# 68_Ethernet-GEPHY_RGMII1.net
KiCad netlist of a schematic drawn in Altium Designer
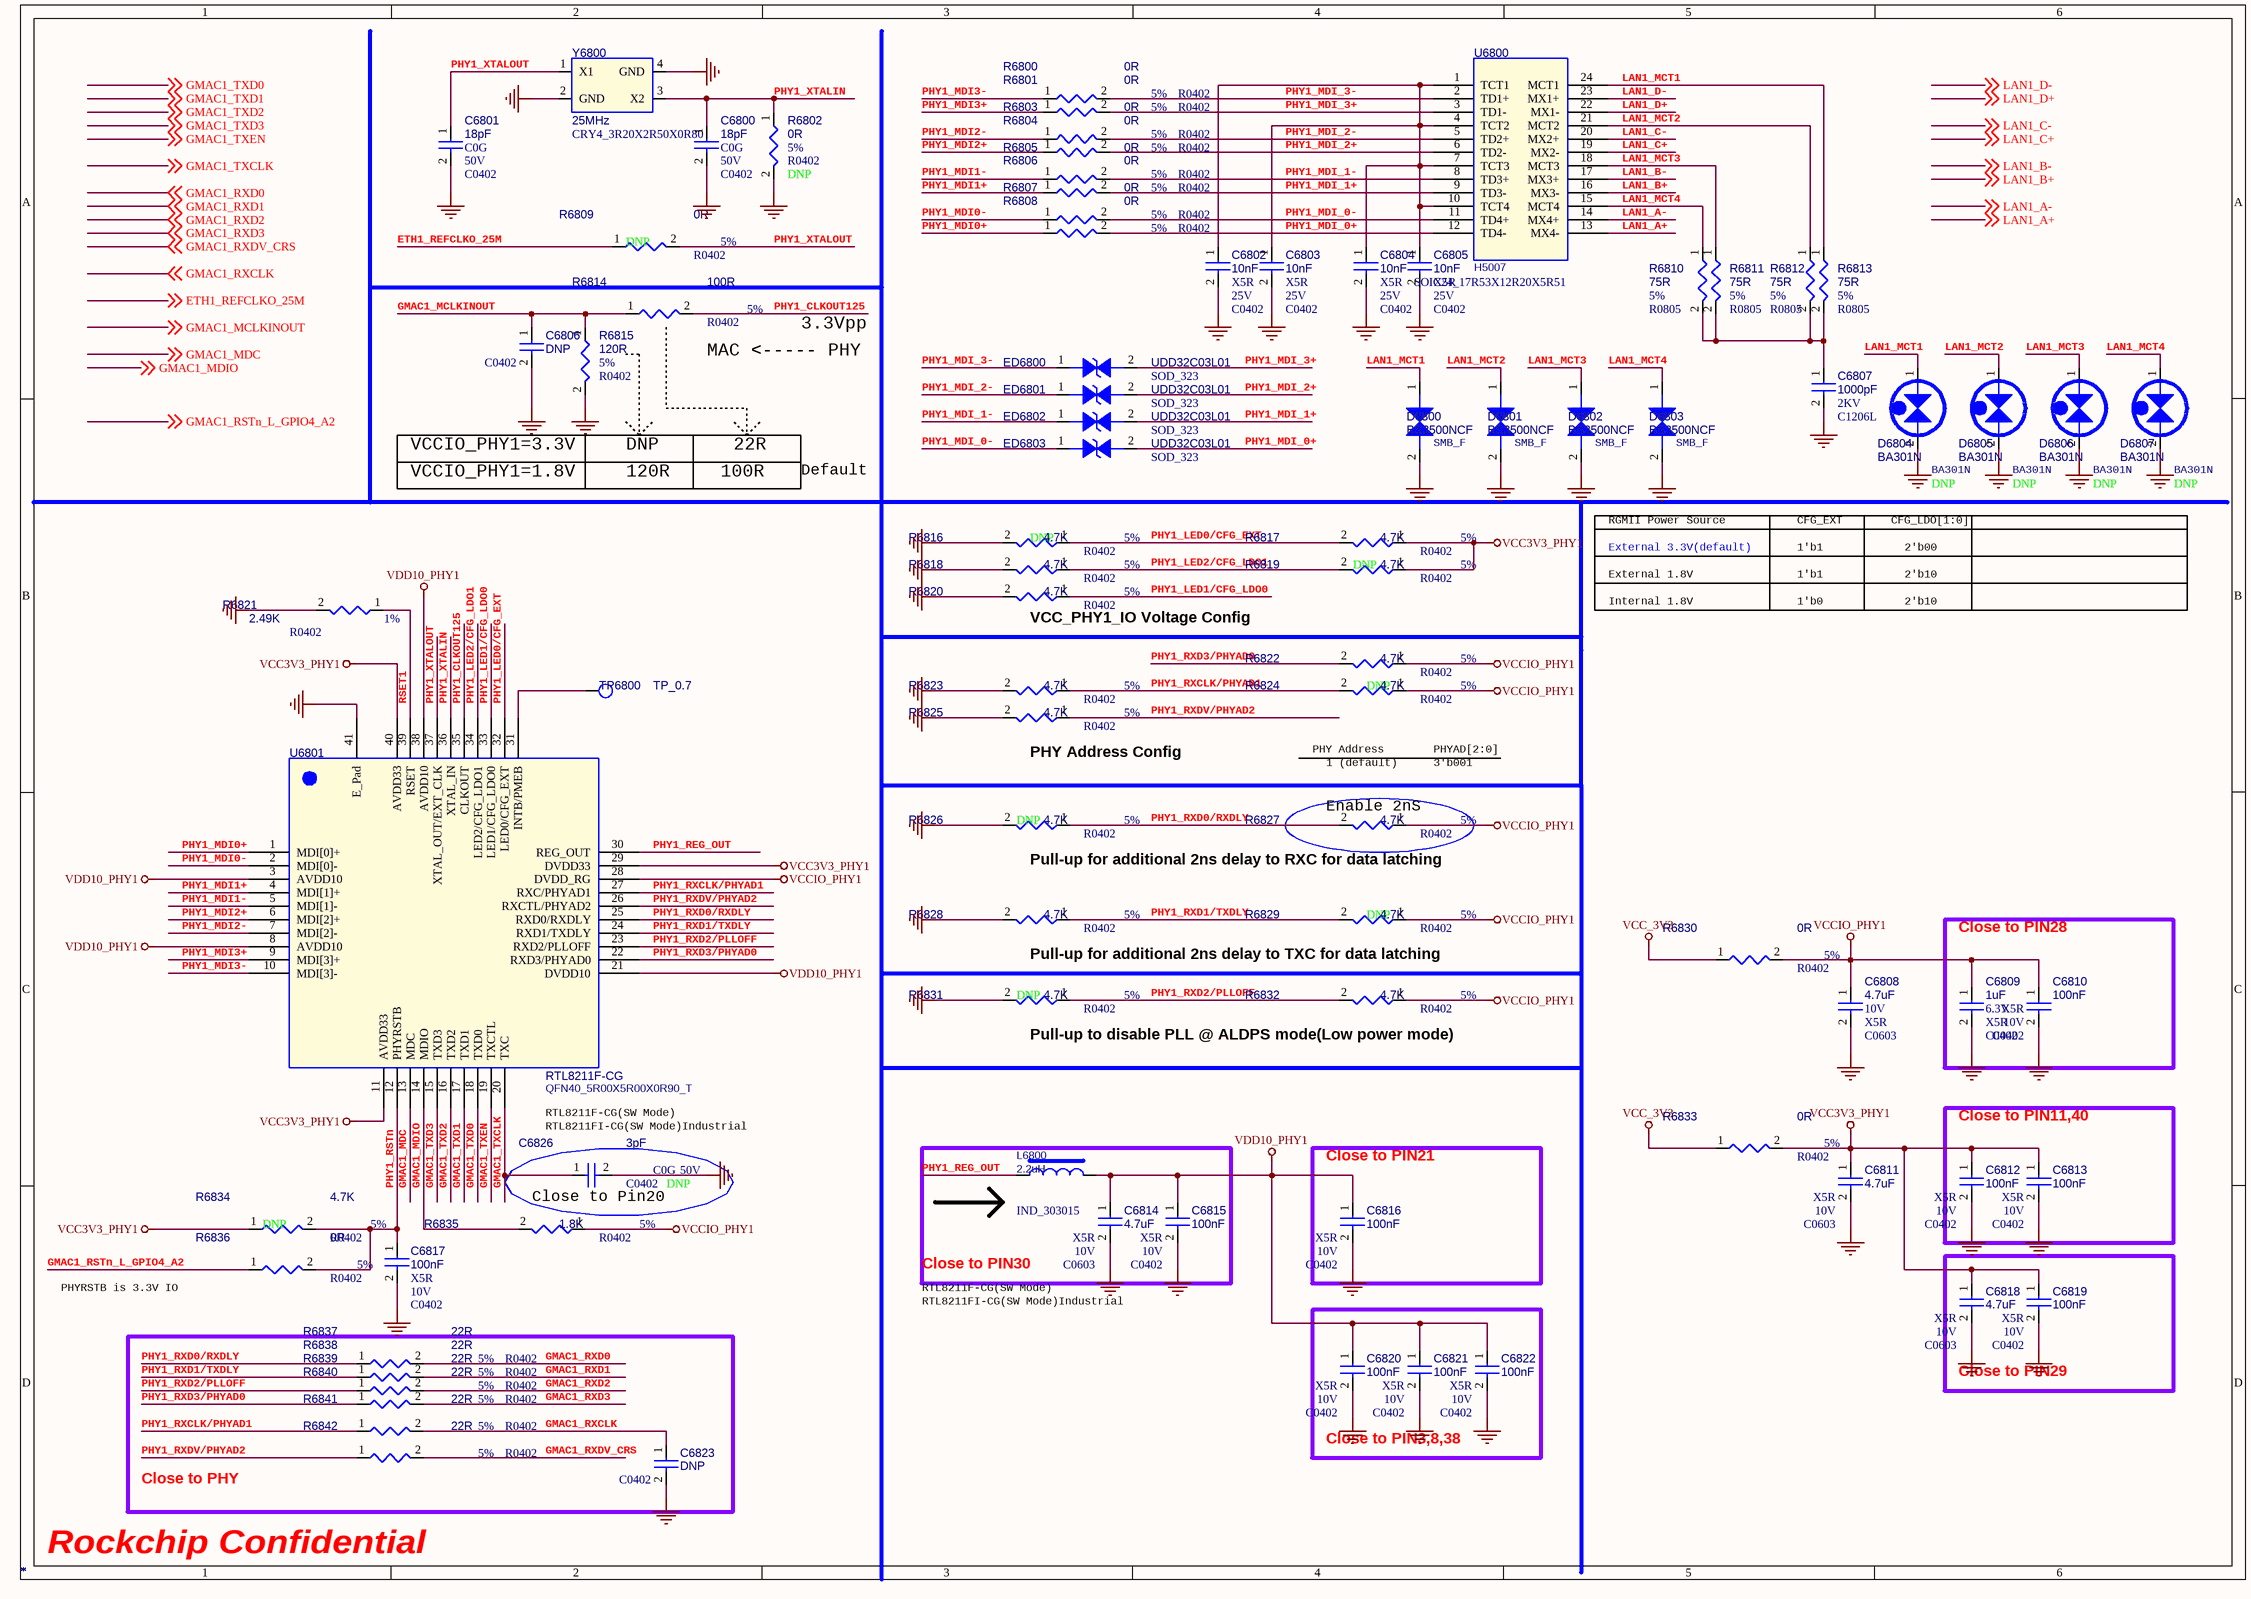
[diagram p0: 68.Ethernet-GEPHY_RGMII1.SchDoc]

(export (version "E")
  (design (tool "Eeschema 10.0.6"))
  (components
    (comp (ref "C6800")
      (value "*")
      (footprint "C0402")
      (description "cap,18.00pF,+/-5%,50V,C0G,C0402")
      (fields
        (field (name "VOLTAGE") "50V")
        (field (name "PCB FOOTPRINT") "C0402")
        (field (name "DIELECTRIC") "C0G")
        (field (name "TOLERANCE") "5%")
        (field (name "MANUFACTURER") "TDK")
        (field (name "ALTIUM_UNNAMED_1") "18pF")
        (field (name "CREATED BY") "JJJ")
      )
      (libsource (lib "*") (part "CAP NP"))
    )
    (comp (ref "C6801")
      (value "*")
      (footprint "C0402")
      (description "cap,18.00pF,+/-5%,50V,C0G,C0402")
      (fields
        (field (name "VOLTAGE") "50V")
        (field (name "PCB FOOTPRINT") "C0402")
        (field (name "DIELECTRIC") "C0G")
        (field (name "TOLERANCE") "5%")
        (field (name "MANUFACTURER") "TDK")
        (field (name "ALTIUM_UNNAMED_1") "18pF")
        (field (name "CREATED BY") "JJJ")
      )
      (libsource (lib "*") (part "CAP NP"))
    )
    (comp (ref "C6802")
      (value "*")
      (footprint "C0402")
      (description "cap,10.00nF,+/-10%,25V,X5R,C0402")
      (fields
        (field (name "VOLTAGE") "25V")
        (field (name "PCB FOOTPRINT") "C0402")
        (field (name "DIELECTRIC") "X5R")
        (field (name "MANUFACTURER") "TDK")
        (field (name "TOLERANCE") "10%")
        (field (name "ALTIUM_UNNAMED_1") "10nF")
        (field (name "CREATED BY") "JJJ")
      )
      (libsource (lib "*") (part "CAP NP"))
    )
    (comp (ref "C6803")
      (value "*")
      (footprint "C0402")
      (description "cap,10.00nF,+/-10%,25V,X5R,C0402")
      (fields
        (field (name "VOLTAGE") "25V")
        (field (name "PCB FOOTPRINT") "C0402")
        (field (name "DIELECTRIC") "X5R")
        (field (name "MANUFACTURER") "TDK")
        (field (name "TOLERANCE") "10%")
        (field (name "ALTIUM_UNNAMED_1") "10nF")
        (field (name "CREATED BY") "JJJ")
      )
      (libsource (lib "*") (part "CAP NP"))
    )
    (comp (ref "C6804")
      (value "*")
      (footprint "C0402")
      (description "cap,10.00nF,+/-10%,25V,X5R,C0402")
      (fields
        (field (name "VOLTAGE") "25V")
        (field (name "PCB FOOTPRINT") "C0402")
        (field (name "DIELECTRIC") "X5R")
        (field (name "TOLERANCE") "10%")
        (field (name "MANUFACTURER") "TDK")
        (field (name "ALTIUM_UNNAMED_1") "10nF")
        (field (name "CREATED BY") "JJJ")
      )
      (libsource (lib "*") (part "CAP NP"))
    )
    (comp (ref "C6805")
      (value "*")
      (footprint "C0402")
      (description "cap,10.00nF,+/-10%,25V,X5R,C0402")
      (fields
        (field (name "VOLTAGE") "25V")
        (field (name "PCB FOOTPRINT") "C0402")
        (field (name "DIELECTRIC") "X5R")
        (field (name "TOLERANCE") "10%")
        (field (name "MANUFACTURER") "TDK")
        (field (name "ALTIUM_UNNAMED_1") "10nF")
        (field (name "CREATED BY") "JJJ")
      )
      (libsource (lib "*") (part "CAP NP"))
    )
    (comp (ref "C6806")
      (value "*")
      (footprint "C0402")
      (description "Did Not Place.")
      (fields
        (field (name "PCB FOOTPRINT") "C0402")
        (field (name "ALTIUM_UNNAMED_1") "DNP")
        (field (name "CREATED BY") "JJJ")
      )
      (libsource (lib "*") (part "CAP NP"))
    )
    (comp (ref "C6807")
      (value "*")
      (footprint "C1206L")
      (description "ёЯС№µзИЭ,1000pF/2KV,C1206")
      (fields
        (field (name "VOLTAGE") "2KV")
        (field (name "PCB FOOTPRINT") "C1206L")
        (field (name "TOLERANCE") "20%")
        (field (name "ALTIUM_UNNAMED_1") "1000pF")
        (field (name "CREATED BY") "JJJ")
      )
      (libsource (lib "*") (part "CAP NP"))
    )
    (comp (ref "C6808")
      (value "*")
      (footprint "C0603")
      (description "cap,4.70uF,+/-10%,10V,X5R,C0603")
      (fields
        (field (name "VOLTAGE") "10V")
        (field (name "PCB FOOTPRINT") "C0603")
        (field (name "DIELECTRIC") "X5R")
        (field (name "TOLERANCE") "10%")
        (field (name "MANUFACTURER") "TDK")
        (field (name "ALTIUM_UNNAMED_1") "4.7uF")
        (field (name "CREATED BY") "JJJ")
      )
      (libsource (lib "*") (part "CAP NP"))
    )
    (comp (ref "C6809")
      (value "*")
      (footprint "C0402")
      (description "cap,1.00uF,+/-10%,6.3V,X5R,C0402")
      (fields
        (field (name "VOLTAGE") "6.3V")
        (field (name "PCB FOOTPRINT") "C0402")
        (field (name "DIELECTRIC") "X5R")
        (field (name "TOLERANCE") "10%")
        (field (name "MANUFACTURER") "TDK")
        (field (name "ALTIUM_UNNAMED_1") "1uF")
        (field (name "CREATED BY") "JJJ")
      )
      (libsource (lib "*") (part "CAP NP"))
    )
    (comp (ref "C6810")
      (value "*")
      (footprint "C0402")
      (description "cap,100.00nF,+/-10%,10V,X5R,C0402")
      (fields
        (field (name "VOLTAGE") "10V")
        (field (name "PCB FOOTPRINT") "C0402")
        (field (name "DIELECTRIC") "X5R")
        (field (name "TOLERANCE") "10%")
        (field (name "MANUFACTURER") "TDK")
        (field (name "ALTIUM_UNNAMED_1") "100nF")
        (field (name "CREATED BY") "JJJ")
      )
      (libsource (lib "*") (part "CAP NP"))
    )
    (comp (ref "C6811")
      (value "*")
      (footprint "C0603")
      (description "cap,4.70uF,+/-10%,10V,X5R,C0603")
      (fields
        (field (name "VOLTAGE") "10V")
        (field (name "PCB FOOTPRINT") "C0603")
        (field (name "DIELECTRIC") "X5R")
        (field (name "MANUFACTURER") "TDK")
        (field (name "TOLERANCE") "10%")
        (field (name "ALTIUM_UNNAMED_1") "4.7uF")
        (field (name "CREATED BY") "JJJ")
      )
      (libsource (lib "*") (part "CAP NP"))
    )
    (comp (ref "C6812")
      (value "*")
      (footprint "C0402")
      (description "cap,100.00nF,+/-10%,10V,X5R,C0402")
      (fields
        (field (name "VOLTAGE") "10V")
        (field (name "PCB FOOTPRINT") "C0402")
        (field (name "DIELECTRIC") "X5R")
        (field (name "TOLERANCE") "10%")
        (field (name "MANUFACTURER") "TDK")
        (field (name "ALTIUM_UNNAMED_1") "100nF")
        (field (name "CREATED BY") "JJJ")
      )
      (libsource (lib "*") (part "CAP NP"))
    )
    (comp (ref "C6813")
      (value "*")
      (footprint "C0402")
      (description "cap,100.00nF,+/-10%,10V,X5R,C0402")
      (fields
        (field (name "VOLTAGE") "10V")
        (field (name "PCB FOOTPRINT") "C0402")
        (field (name "DIELECTRIC") "X5R")
        (field (name "TOLERANCE") "10%")
        (field (name "MANUFACTURER") "TDK")
        (field (name "ALTIUM_UNNAMED_1") "100nF")
        (field (name "CREATED BY") "JJJ")
      )
      (libsource (lib "*") (part "CAP NP"))
    )
    (comp (ref "C6814")
      (value "*")
      (footprint "C0603")
      (description "cap,4.70uF,+/-10%,10V,X5R,C0603")
      (fields
        (field (name "VOLTAGE") "10V")
        (field (name "PCB FOOTPRINT") "C0603")
        (field (name "DIELECTRIC") "X5R")
        (field (name "MANUFACTURER") "TDK")
        (field (name "TOLERANCE") "10%")
        (field (name "ALTIUM_UNNAMED_1") "4.7uF")
        (field (name "CREATED BY") "JJJ")
      )
      (libsource (lib "*") (part "CAP NP"))
    )
    (comp (ref "C6815")
      (value "*")
      (footprint "C0402")
      (description "cap,100.00nF,+/-10%,10V,X5R,C0402")
      (fields
        (field (name "VOLTAGE") "10V")
        (field (name "PCB FOOTPRINT") "C0402")
        (field (name "DIELECTRIC") "X5R")
        (field (name "MANUFACTURER") "TDK")
        (field (name "TOLERANCE") "10%")
        (field (name "ALTIUM_UNNAMED_1") "100nF")
        (field (name "CREATED BY") "JJJ")
      )
      (libsource (lib "*") (part "CAP NP"))
    )
    (comp (ref "C6816")
      (value "*")
      (footprint "C0402")
      (description "cap,100.00nF,+/-10%,10V,X5R,C0402")
      (fields
        (field (name "VOLTAGE") "10V")
        (field (name "PCB FOOTPRINT") "C0402")
        (field (name "DIELECTRIC") "X5R")
        (field (name "MANUFACTURER") "TDK")
        (field (name "TOLERANCE") "10%")
        (field (name "ALTIUM_UNNAMED_1") "100nF")
        (field (name "CREATED BY") "JJJ")
      )
      (libsource (lib "*") (part "CAP NP"))
    )
    (comp (ref "C6817")
      (value "*")
      (footprint "C0402")
      (description "cap,100.00nF,+/-10%,10V,X5R,C0402")
      (fields
        (field (name "VOLTAGE") "10V")
        (field (name "PCB FOOTPRINT") "C0402")
        (field (name "DIELECTRIC") "X5R")
        (field (name "MANUFACTURER") "TDK")
        (field (name "TOLERANCE") "10%")
        (field (name "ALTIUM_UNNAMED_1") "100nF")
        (field (name "CREATED BY") "JJJ")
      )
      (libsource (lib "*") (part "CAP NP"))
    )
    (comp (ref "C6818")
      (value "*")
      (footprint "C0603")
      (description "cap,4.70uF,+/-10%,10V,X5R,C0603")
      (fields
        (field (name "VOLTAGE") "10V")
        (field (name "PCB FOOTPRINT") "C0603")
        (field (name "DIELECTRIC") "X5R")
        (field (name "MANUFACTURER") "TDK")
        (field (name "TOLERANCE") "10%")
        (field (name "ALTIUM_UNNAMED_1") "4.7uF")
        (field (name "CREATED BY") "JJJ")
      )
      (libsource (lib "*") (part "CAP NP"))
    )
    (comp (ref "C6819")
      (value "*")
      (footprint "C0402")
      (description "cap,100.00nF,+/-10%,10V,X5R,C0402")
      (fields
        (field (name "VOLTAGE") "10V")
        (field (name "PCB FOOTPRINT") "C0402")
        (field (name "DIELECTRIC") "X5R")
        (field (name "TOLERANCE") "10%")
        (field (name "MANUFACTURER") "TDK")
        (field (name "ALTIUM_UNNAMED_1") "100nF")
        (field (name "CREATED BY") "JJJ")
      )
      (libsource (lib "*") (part "CAP NP"))
    )
    (comp (ref "C6820")
      (value "*")
      (footprint "C0402")
      (description "cap,100.00nF,+/-10%,10V,X5R,C0402")
      (fields
        (field (name "VOLTAGE") "10V")
        (field (name "PCB FOOTPRINT") "C0402")
        (field (name "DIELECTRIC") "X5R")
        (field (name "TOLERANCE") "10%")
        (field (name "MANUFACTURER") "TDK")
        (field (name "ALTIUM_UNNAMED_1") "100nF")
        (field (name "CREATED BY") "JJJ")
      )
      (libsource (lib "*") (part "CAP NP"))
    )
    (comp (ref "C6821")
      (value "*")
      (footprint "C0402")
      (description "cap,100.00nF,+/-10%,10V,X5R,C0402")
      (fields
        (field (name "VOLTAGE") "10V")
        (field (name "PCB FOOTPRINT") "C0402")
        (field (name "DIELECTRIC") "X5R")
        (field (name "TOLERANCE") "10%")
        (field (name "MANUFACTURER") "TDK")
        (field (name "ALTIUM_UNNAMED_1") "100nF")
        (field (name "CREATED BY") "JJJ")
      )
      (libsource (lib "*") (part "CAP NP"))
    )
    (comp (ref "C6822")
      (value "*")
      (footprint "C0402")
      (description "cap,100.00nF,+/-10%,10V,X5R,C0402")
      (fields
        (field (name "VOLTAGE") "10V")
        (field (name "PCB FOOTPRINT") "C0402")
        (field (name "DIELECTRIC") "X5R")
        (field (name "TOLERANCE") "10%")
        (field (name "MANUFACTURER") "TDK")
        (field (name "ALTIUM_UNNAMED_1") "100nF")
        (field (name "CREATED BY") "JJJ")
      )
      (libsource (lib "*") (part "CAP NP"))
    )
    (comp (ref "C6823")
      (value "*")
      (footprint "C0402")
      (description "Did Not Place.")
      (fields
        (field (name "PCB FOOTPRINT") "C0402")
        (field (name "ALTIUM_UNNAMED_1") "DNP")
        (field (name "CREATED BY") "JJJ")
      )
      (libsource (lib "*") (part "CAP NP"))
    )
    (comp (ref "C6826")
      (value "*")
      (footprint "C0402")
      (description "cap,3.00pF,+/-0.25,50V,C0G,C0402")
      (fields
        (field (name "VOLTAGE") "50V")
        (field (name "PCB FOOTPRINT") "C0402")
        (field (name "DIELECTRIC") "C0G")
        (field (name "OPTION") "DNP")
        (field (name "TOLERANCE") "+/-0.25pF")
        (field (name "MANUFACTURER") "TDK")
        (field (name "ALTIUM_UNNAMED_1") "3pF")
        (field (name "CREATED BY") "JJJ")
      )
      (libsource (lib "*") (part "CAP NP"))
    )
    (comp (ref "D6800")
      (value "*")
      (footprint "BA301N")
      (fields (field (name "PCB FOOTPRINT") "SMB_F") (field (name "ALTIUM_UNNAMED_1") "BS3500NCF"))
      (libsource (lib "*") (part "BA301N_3"))
    )
    (comp (ref "D6801")
      (value "*")
      (footprint "BA301N")
      (fields (field (name "PCB FOOTPRINT") "SMB_F") (field (name "ALTIUM_UNNAMED_1") "BS3500NCF"))
      (libsource (lib "*") (part "BA301N_3"))
    )
    (comp (ref "D6802")
      (value "*")
      (footprint "BA301N")
      (fields (field (name "PCB FOOTPRINT") "SMB_F") (field (name "ALTIUM_UNNAMED_1") "BS3500NCF"))
      (libsource (lib "*") (part "BA301N_3"))
    )
    (comp (ref "D6803")
      (value "*")
      (footprint "BA301N")
      (fields (field (name "PCB FOOTPRINT") "SMB_F") (field (name "ALTIUM_UNNAMED_1") "BS3500NCF"))
      (libsource (lib "*") (part "BA301N_3"))
    )
    (comp (ref "D6804")
      (value "*")
      (footprint "BA301N")
      (fields
        (field (name "PCB FOOTPRINT") "BA301N")
        (field (name "OPTION") "DNP")
        (field (name "ALTIUM_UNNAMED_1") "BA301N")
      )
      (libsource (lib "*") (part "BA301N_1"))
    )
    (comp (ref "D6805")
      (value "*")
      (footprint "BA301N")
      (fields
        (field (name "PCB FOOTPRINT") "BA301N")
        (field (name "OPTION") "DNP")
        (field (name "ALTIUM_UNNAMED_1") "BA301N")
      )
      (libsource (lib "*") (part "BA301N_1"))
    )
    (comp (ref "D6806")
      (value "*")
      (footprint "BA301N")
      (fields
        (field (name "PCB FOOTPRINT") "BA301N")
        (field (name "OPTION") "DNP")
        (field (name "ALTIUM_UNNAMED_1") "BA301N")
      )
      (libsource (lib "*") (part "BA301N_1"))
    )
    (comp (ref "D6807")
      (value "*")
      (footprint "BA301N")
      (fields
        (field (name "PCB FOOTPRINT") "BA301N")
        (field (name "OPTION") "DNP")
        (field (name "ALTIUM_UNNAMED_1") "BA301N")
      )
      (libsource (lib "*") (part "BA301N_1"))
    )
    (comp (ref "ED6800")
      (value "*")
      (footprint "SOD_323")
      (description "Transient Voltage Suppressor,0.8pF")
      (fields
        (field (name "PCB FOOTPRINT") "SOD_323")
        (field (name "MANUFACTURER") "WillSemi(О¤¶ы°лµјМе)")
        (field (name "ALTIUM_UNNAMED_1") "UDD32C03L01")
        (field (name "CREATED BY") "JJJ")
      )
      (libsource (lib "*") (part "DIODE BI_DIR TRIG"))
    )
    (comp (ref "ED6801")
      (value "*")
      (footprint "SOD_323")
      (description "Transient Voltage Suppressor,0.8pF")
      (fields
        (field (name "PCB FOOTPRINT") "SOD_323")
        (field (name "MANUFACTURER") "WillSemi(О¤¶ы°лµјМе)")
        (field (name "ALTIUM_UNNAMED_1") "UDD32C03L01")
        (field (name "CREATED BY") "JJJ")
      )
      (libsource (lib "*") (part "DIODE BI_DIR TRIG"))
    )
    (comp (ref "ED6802")
      (value "*")
      (footprint "SOD_323")
      (description "Transient Voltage Suppressor,0.8pF")
      (fields
        (field (name "PCB FOOTPRINT") "SOD_323")
        (field (name "MANUFACTURER") "WillSemi(О¤¶ы°лµјМе)")
        (field (name "ALTIUM_UNNAMED_1") "UDD32C03L01")
        (field (name "CREATED BY") "JJJ")
      )
      (libsource (lib "*") (part "DIODE BI_DIR TRIG"))
    )
    (comp (ref "ED6803")
      (value "*")
      (footprint "SOD_323")
      (description "Transient Voltage Suppressor,0.8pF")
      (fields
        (field (name "PCB FOOTPRINT") "SOD_323")
        (field (name "MANUFACTURER") "WillSemi(О¤¶ы°лµјМе)")
        (field (name "ALTIUM_UNNAMED_1") "UDD32C03L01")
        (field (name "CREATED BY") "JJJ")
      )
      (libsource (lib "*") (part "DIODE BI_DIR TRIG"))
    )
    (comp (ref "L6800")
      (value "*")
      (footprint "IND_303015")
      (description "Power Inductor,2.2uH,0.3,IND_303015")
      (fields
        (field (name "PCB FOOTPRINT") "IND_303015")
        (field (name "MANUFACTURER") "sunlord")
        (field (name "TOLERANCE") "30%")
        (field (name "ALTIUM_UNNAMED_1") "2.2uH")
        (field (name "CREATED BY") "YTL")
      )
      (libsource (lib "*") (part "INDUCTORS OF FERRITE_Dup1"))
    )
    (comp (ref "R6800")
      (value "*")
      (footprint "R0402")
      (description "НЁУГєсД¤µзЧи,0R,+/-5%,R0402,1/16W.")
      (fields
        (field (name "PCB FOOTPRINT") "R0402")
        (field (name "TOLERANCE") "5%")
        (field (name "MANUFACTURER") "YAGEO")
        (field (name "ALTIUM_UNNAMED_1") "0R")
        (field (name "CREATED BY") "YTL")
      )
      (libsource (lib "*") (part "RESISTOR_Dup1"))
    )
    (comp (ref "R6801")
      (value "*")
      (footprint "R0402")
      (description "НЁУГєсД¤µзЧи,0R,+/-5%,R0402,1/16W.")
      (fields
        (field (name "PCB FOOTPRINT") "R0402")
        (field (name "TOLERANCE") "5%")
        (field (name "MANUFACTURER") "YAGEO")
        (field (name "ALTIUM_UNNAMED_1") "0R")
        (field (name "CREATED BY") "YTL")
      )
      (libsource (lib "*") (part "RESISTOR_Dup1"))
    )
    (comp (ref "R6802")
      (value "*")
      (footprint "R0402")
      (description "НЁУГєсД¤µзЧи,0R,+/-5%,R0402,1/16W.")
      (fields
        (field (name "PCB FOOTPRINT") "R0402")
        (field (name "TOLERANCE") "5%")
        (field (name "MANUFACTURER") "YAGEO")
        (field (name "OPTION") "DNP")
        (field (name "ALTIUM_UNNAMED_1") "0R")
        (field (name "CREATED BY") "YTL")
      )
      (libsource (lib "*") (part "RESISTOR_Dup1"))
    )
    (comp (ref "R6803")
      (value "*")
      (footprint "R0402")
      (description "НЁУГєсД¤µзЧи,0R,+/-5%,R0402,1/16W.")
      (fields
        (field (name "PCB FOOTPRINT") "R0402")
        (field (name "TOLERANCE") "5%")
        (field (name "MANUFACTURER") "YAGEO")
        (field (name "ALTIUM_UNNAMED_1") "0R")
        (field (name "CREATED BY") "YTL")
      )
      (libsource (lib "*") (part "RESISTOR_Dup1"))
    )
    (comp (ref "R6804")
      (value "*")
      (footprint "R0402")
      (description "НЁУГєсД¤µзЧи,0R,+/-5%,R0402,1/16W.")
      (fields
        (field (name "PCB FOOTPRINT") "R0402")
        (field (name "TOLERANCE") "5%")
        (field (name "MANUFACTURER") "YAGEO")
        (field (name "ALTIUM_UNNAMED_1") "0R")
        (field (name "CREATED BY") "YTL")
      )
      (libsource (lib "*") (part "RESISTOR_Dup1"))
    )
    (comp (ref "R6805")
      (value "*")
      (footprint "R0402")
      (description "НЁУГєсД¤µзЧи,0R,+/-5%,R0402,1/16W.")
      (fields
        (field (name "PCB FOOTPRINT") "R0402")
        (field (name "TOLERANCE") "5%")
        (field (name "MANUFACTURER") "YAGEO")
        (field (name "ALTIUM_UNNAMED_1") "0R")
        (field (name "CREATED BY") "YTL")
      )
      (libsource (lib "*") (part "RESISTOR_Dup1"))
    )
    (comp (ref "R6806")
      (value "*")
      (footprint "R0402")
      (description "НЁУГєсД¤µзЧи,0R,+/-5%,R0402,1/16W.")
      (fields
        (field (name "PCB FOOTPRINT") "R0402")
        (field (name "TOLERANCE") "5%")
        (field (name "MANUFACTURER") "YAGEO")
        (field (name "ALTIUM_UNNAMED_1") "0R")
        (field (name "CREATED BY") "YTL")
      )
      (libsource (lib "*") (part "RESISTOR_Dup1"))
    )
    (comp (ref "R6807")
      (value "*")
      (footprint "R0402")
      (description "НЁУГєсД¤µзЧи,0R,+/-5%,R0402,1/16W.")
      (fields
        (field (name "PCB FOOTPRINT") "R0402")
        (field (name "TOLERANCE") "5%")
        (field (name "MANUFACTURER") "YAGEO")
        (field (name "ALTIUM_UNNAMED_1") "0R")
        (field (name "CREATED BY") "YTL")
      )
      (libsource (lib "*") (part "RESISTOR_Dup1"))
    )
    (comp (ref "R6808")
      (value "*")
      (footprint "R0402")
      (description "НЁУГєсД¤µзЧи,0R,+/-5%,R0402,1/16W.")
      (fields
        (field (name "PCB FOOTPRINT") "R0402")
        (field (name "TOLERANCE") "5%")
        (field (name "MANUFACTURER") "YAGEO")
        (field (name "ALTIUM_UNNAMED_1") "0R")
        (field (name "CREATED BY") "YTL")
      )
      (libsource (lib "*") (part "RESISTOR_Dup1"))
    )
    (comp (ref "R6809")
      (value "*")
      (footprint "R0402")
      (description "НЁУГєсД¤µзЧи,0R,+/-5%,R0402,1/16W.")
      (fields
        (field (name "PCB FOOTPRINT") "R0402")
        (field (name "TOLERANCE") "5%")
        (field (name "OPTION") "DNP")
        (field (name "MANUFACTURER") "YAGEO")
        (field (name "ALTIUM_UNNAMED_1") "0R")
        (field (name "CREATED BY") "YTL")
      )
      (libsource (lib "*") (part "RESISTOR_Dup1"))
    )
    (comp (ref "R6810")
      (value "*")
      (footprint "R0402")
      (description "НЁУГєсД¤µзЧи,75R,+/-5%,R0805,1/8W.")
      (fields
        (field (name "PCB FOOTPRINT") "R0805")
        (field (name "TOLERANCE") "5%")
        (field (name "MANUFACTURER") "YAGEO")
        (field (name "ALTIUM_UNNAMED_1") "75R")
        (field (name "CREATED BY") "YTL")
      )
      (libsource (lib "*") (part "RESISTOR_Dup1"))
    )
    (comp (ref "R6811")
      (value "*")
      (footprint "R0402")
      (description "НЁУГєсД¤µзЧи,75R,+/-5%,R0805,1/8W.")
      (fields
        (field (name "PCB FOOTPRINT") "R0805")
        (field (name "TOLERANCE") "5%")
        (field (name "MANUFACTURER") "YAGEO")
        (field (name "ALTIUM_UNNAMED_1") "75R")
        (field (name "CREATED BY") "YTL")
      )
      (libsource (lib "*") (part "RESISTOR_Dup1"))
    )
    (comp (ref "R6812")
      (value "*")
      (footprint "R0402")
      (description "НЁУГєсД¤µзЧи,75R,+/-5%,R0805,1/8W.")
      (fields
        (field (name "PCB FOOTPRINT") "R0805")
        (field (name "TOLERANCE") "5%")
        (field (name "MANUFACTURER") "YAGEO")
        (field (name "ALTIUM_UNNAMED_1") "75R")
        (field (name "CREATED BY") "YTL")
      )
      (libsource (lib "*") (part "RESISTOR_Dup1"))
    )
    (comp (ref "R6813")
      (value "*")
      (footprint "R0402")
      (description "НЁУГєсД¤µзЧи,75R,+/-5%,R0805,1/8W.")
      (fields
        (field (name "PCB FOOTPRINT") "R0805")
        (field (name "TOLERANCE") "5%")
        (field (name "MANUFACTURER") "YAGEO")
        (field (name "ALTIUM_UNNAMED_1") "75R")
        (field (name "CREATED BY") "YTL")
      )
      (libsource (lib "*") (part "RESISTOR_Dup1"))
    )
    (comp (ref "R6814")
      (value "*")
      (footprint "R0402")
      (description "НЁУГєсД¤µзЧи,100R,+/-5%,R0402,1/16W.")
      (fields
        (field (name "PCB FOOTPRINT") "R0402")
        (field (name "TOLERANCE") "5%")
        (field (name "MANUFACTURER") "YAGEO")
        (field (name "ALTIUM_UNNAMED_1") "100R")
        (field (name "CREATED BY") "YTL")
      )
      (libsource (lib "*") (part "RESISTOR_Dup1"))
    )
    (comp (ref "R6815")
      (value "*")
      (footprint "R0402")
      (description "НЁУГєсД¤µзЧи,120R,+/-5%,R0402,1/16W.")
      (fields
        (field (name "PCB FOOTPRINT") "R0402")
        (field (name "TOLERANCE") "5%")
        (field (name "MANUFACTURER") "YAGEO")
        (field (name "ALTIUM_UNNAMED_1") "120R")
        (field (name "CREATED BY") "YTL")
      )
      (libsource (lib "*") (part "RESISTOR_Dup1"))
    )
    (comp (ref "R6816")
      (value "*")
      (footprint "R0402")
      (description "НЁУГєсД¤µзЧи,4K7,+/-5%,R0402,1/16W.")
      (fields
        (field (name "PCB FOOTPRINT") "R0402")
        (field (name "TOLERANCE") "5%")
        (field (name "MANUFACTURER") "YAGEO")
        (field (name "OPTION") "DNP")
        (field (name "ALTIUM_UNNAMED_1") "4.7K")
        (field (name "CREATED BY") "YTL")
      )
      (libsource (lib "*") (part "RESISTOR_Dup1"))
    )
    (comp (ref "R6817")
      (value "*")
      (footprint "R0402")
      (description "НЁУГєсД¤µзЧи,4K7,+/-5%,R0402,1/16W.")
      (fields
        (field (name "PCB FOOTPRINT") "R0402")
        (field (name "TOLERANCE") "5%")
        (field (name "MANUFACTURER") "YAGEO")
        (field (name "ALTIUM_UNNAMED_1") "4.7K")
        (field (name "CREATED BY") "YTL")
      )
      (libsource (lib "*") (part "RESISTOR_Dup1"))
    )
    (comp (ref "R6818")
      (value "*")
      (footprint "R0402")
      (description "НЁУГєсД¤µзЧи,4K7,+/-5%,R0402,1/16W.")
      (fields
        (field (name "PCB FOOTPRINT") "R0402")
        (field (name "TOLERANCE") "5%")
        (field (name "MANUFACTURER") "YAGEO")
        (field (name "ALTIUM_UNNAMED_1") "4.7K")
        (field (name "CREATED BY") "YTL")
      )
      (libsource (lib "*") (part "RESISTOR_Dup1"))
    )
    (comp (ref "R6819")
      (value "*")
      (footprint "R0402")
      (description "НЁУГєсД¤µзЧи,4K7,+/-5%,R0402,1/16W.")
      (fields
        (field (name "PCB FOOTPRINT") "R0402")
        (field (name "TOLERANCE") "5%")
        (field (name "OPTION") "DNP")
        (field (name "MANUFACTURER") "YAGEO")
        (field (name "ALTIUM_UNNAMED_1") "4.7K")
        (field (name "CREATED BY") "YTL")
      )
      (libsource (lib "*") (part "RESISTOR_Dup1"))
    )
    (comp (ref "R6820")
      (value "*")
      (footprint "R0402")
      (description "НЁУГєсД¤µзЧи,4K7,+/-5%,R0402,1/16W.")
      (fields
        (field (name "PCB FOOTPRINT") "R0402")
        (field (name "TOLERANCE") "5%")
        (field (name "MANUFACTURER") "YAGEO")
        (field (name "ALTIUM_UNNAMED_1") "4.7K")
        (field (name "CREATED BY") "YTL")
      )
      (libsource (lib "*") (part "RESISTOR_Dup1"))
    )
    (comp (ref "R6821")
      (value "*")
      (footprint "R0402")
      (description "НЁУГєсД¤µзЧи,2K49,+/-1%,R0402,1/16W.")
      (fields
        (field (name "PCB FOOTPRINT") "R0402")
        (field (name "TOLERANCE") "1%")
        (field (name "MANUFACTURER") "YAGEO")
        (field (name "ALTIUM_UNNAMED_1") "2.49K")
        (field (name "CREATED BY") "YTL")
      )
      (libsource (lib "*") (part "RESISTOR_Dup1"))
    )
    (comp (ref "R6822")
      (value "*")
      (footprint "R0402")
      (description "НЁУГєсД¤µзЧи,4K7,+/-5%,R0402,1/16W.")
      (fields
        (field (name "PCB FOOTPRINT") "R0402")
        (field (name "TOLERANCE") "5%")
        (field (name "MANUFACTURER") "YAGEO")
        (field (name "ALTIUM_UNNAMED_1") "4.7K")
        (field (name "CREATED BY") "YTL")
      )
      (libsource (lib "*") (part "RESISTOR_Dup1"))
    )
    (comp (ref "R6823")
      (value "*")
      (footprint "R0402")
      (description "НЁУГєсД¤µзЧи,4K7,+/-5%,R0402,1/16W.")
      (fields
        (field (name "PCB FOOTPRINT") "R0402")
        (field (name "TOLERANCE") "5%")
        (field (name "MANUFACTURER") "YAGEO")
        (field (name "ALTIUM_UNNAMED_1") "4.7K")
        (field (name "CREATED BY") "YTL")
      )
      (libsource (lib "*") (part "RESISTOR_Dup1"))
    )
    (comp (ref "R6824")
      (value "*")
      (footprint "R0402")
      (description "НЁУГєсД¤µзЧи,4K7,+/-5%,R0402,1/16W.")
      (fields
        (field (name "PCB FOOTPRINT") "R0402")
        (field (name "TOLERANCE") "5%")
        (field (name "MANUFACTURER") "YAGEO")
        (field (name "OPTION") "DNP")
        (field (name "ALTIUM_UNNAMED_1") "4.7K")
        (field (name "CREATED BY") "YTL")
      )
      (libsource (lib "*") (part "RESISTOR_Dup1"))
    )
    (comp (ref "R6825")
      (value "*")
      (footprint "R0402")
      (description "НЁУГєсД¤µзЧи,4K7,+/-5%,R0402,1/16W.")
      (fields
        (field (name "PCB FOOTPRINT") "R0402")
        (field (name "TOLERANCE") "5%")
        (field (name "MANUFACTURER") "YAGEO")
        (field (name "ALTIUM_UNNAMED_1") "4.7K")
        (field (name "CREATED BY") "YTL")
      )
      (libsource (lib "*") (part "RESISTOR_Dup1"))
    )
    (comp (ref "R6826")
      (value "*")
      (footprint "R0402")
      (description "НЁУГєсД¤µзЧи,4K7,+/-5%,R0402,1/16W.")
      (fields
        (field (name "PCB FOOTPRINT") "R0402")
        (field (name "TOLERANCE") "5%")
        (field (name "OPTION") "DNP")
        (field (name "MANUFACTURER") "YAGEO")
        (field (name "ALTIUM_UNNAMED_1") "4.7K")
        (field (name "CREATED BY") "YTL")
      )
      (libsource (lib "*") (part "RESISTOR_Dup1"))
    )
    (comp (ref "R6827")
      (value "*")
      (footprint "R0402")
      (description "НЁУГєсД¤µзЧи,4K7,+/-5%,R0402,1/16W.")
      (fields
        (field (name "PCB FOOTPRINT") "R0402")
        (field (name "TOLERANCE") "5%")
        (field (name "MANUFACTURER") "YAGEO")
        (field (name "ALTIUM_UNNAMED_1") "4.7K")
        (field (name "CREATED BY") "YTL")
      )
      (libsource (lib "*") (part "RESISTOR_Dup1"))
    )
    (comp (ref "R6828")
      (value "*")
      (footprint "R0402")
      (description "НЁУГєсД¤µзЧи,4K7,+/-5%,R0402,1/16W.")
      (fields
        (field (name "PCB FOOTPRINT") "R0402")
        (field (name "TOLERANCE") "5%")
        (field (name "MANUFACTURER") "YAGEO")
        (field (name "ALTIUM_UNNAMED_1") "4.7K")
        (field (name "CREATED BY") "YTL")
      )
      (libsource (lib "*") (part "RESISTOR_Dup1"))
    )
    (comp (ref "R6829")
      (value "*")
      (footprint "R0402")
      (description "НЁУГєсД¤µзЧи,4K7,+/-5%,R0402,1/16W.")
      (fields
        (field (name "PCB FOOTPRINT") "R0402")
        (field (name "TOLERANCE") "5%")
        (field (name "MANUFACTURER") "YAGEO")
        (field (name "OPTION") "DNP")
        (field (name "ALTIUM_UNNAMED_1") "4.7K")
        (field (name "CREATED BY") "YTL")
      )
      (libsource (lib "*") (part "RESISTOR_Dup1"))
    )
    (comp (ref "R6830")
      (value "*")
      (footprint "R0402")
      (description "НЁУГєсД¤µзЧи,0R,+/-5%,R0402,1/16W.")
      (fields
        (field (name "PCB FOOTPRINT") "R0402")
        (field (name "TOLERANCE") "5%")
        (field (name "MANUFACTURER") "YAGEO")
        (field (name "ALTIUM_UNNAMED_1") "0R")
        (field (name "CREATED BY") "YTL")
      )
      (libsource (lib "*") (part "RESISTOR_Dup1"))
    )
    (comp (ref "R6831")
      (value "*")
      (footprint "R0402")
      (description "НЁУГєсД¤µзЧи,4K7,+/-5%,R0402,1/16W.")
      (fields
        (field (name "PCB FOOTPRINT") "R0402")
        (field (name "TOLERANCE") "5%")
        (field (name "OPTION") "DNP")
        (field (name "MANUFACTURER") "YAGEO")
        (field (name "ALTIUM_UNNAMED_1") "4.7K")
        (field (name "CREATED BY") "YTL")
      )
      (libsource (lib "*") (part "RESISTOR_Dup1"))
    )
    (comp (ref "R6832")
      (value "*")
      (footprint "R0402")
      (description "НЁУГєсД¤µзЧи,4K7,+/-5%,R0402,1/16W.")
      (fields
        (field (name "PCB FOOTPRINT") "R0402")
        (field (name "TOLERANCE") "5%")
        (field (name "MANUFACTURER") "YAGEO")
        (field (name "ALTIUM_UNNAMED_1") "4.7K")
        (field (name "CREATED BY") "YTL")
      )
      (libsource (lib "*") (part "RESISTOR_Dup1"))
    )
    (comp (ref "R6833")
      (value "*")
      (footprint "R0402")
      (description "НЁУГєсД¤µзЧи,0R,+/-5%,R0402,1/16W.")
      (fields
        (field (name "PCB FOOTPRINT") "R0402")
        (field (name "TOLERANCE") "5%")
        (field (name "MANUFACTURER") "YAGEO")
        (field (name "ALTIUM_UNNAMED_1") "0R")
        (field (name "CREATED BY") "YTL")
      )
      (libsource (lib "*") (part "RESISTOR_Dup1"))
    )
    (comp (ref "R6834")
      (value "*")
      (footprint "R0402")
      (description "НЁУГєсД¤µзЧи,4K7,+/-5%,R0402,1/16W.")
      (fields
        (field (name "PCB FOOTPRINT") "R0402")
        (field (name "TOLERANCE") "5%")
        (field (name "OPTION") "DNP")
        (field (name "MANUFACTURER") "YAGEO")
        (field (name "ALTIUM_UNNAMED_1") "4.7K")
        (field (name "CREATED BY") "YTL")
      )
      (libsource (lib "*") (part "RESISTOR_Dup1"))
    )
    (comp (ref "R6835")
      (value "*")
      (footprint "R0402")
      (description "НЁУГєсД¤µзЧи,1K8,+/-5%,R0402,1/16W.")
      (fields
        (field (name "PCB FOOTPRINT") "R0402")
        (field (name "TOLERANCE") "5%")
        (field (name "MANUFACTURER") "YAGEO")
        (field (name "ALTIUM_UNNAMED_1") "1.8K")
        (field (name "CREATED BY") "YTL")
      )
      (libsource (lib "*") (part "RESISTOR_Dup1"))
    )
    (comp (ref "R6836")
      (value "*")
      (footprint "R0402")
      (description "НЁУГєсД¤µзЧи,0R,+/-5%,R0402,1/16W.")
      (fields
        (field (name "PCB FOOTPRINT") "R0402")
        (field (name "TOLERANCE") "5%")
        (field (name "MANUFACTURER") "YAGEO")
        (field (name "ALTIUM_UNNAMED_1") "0R")
        (field (name "CREATED BY") "YTL")
      )
      (libsource (lib "*") (part "RESISTOR_Dup1"))
    )
    (comp (ref "R6837")
      (value "*")
      (footprint "R0402")
      (description "НЁУГєсД¤µзЧи,22R,+/-5%,R0402,1/16W.")
      (fields
        (field (name "PCB FOOTPRINT") "R0402")
        (field (name "TOLERANCE") "5%")
        (field (name "MANUFACTURER") "YAGEO")
        (field (name "ALTIUM_UNNAMED_1") "22R")
        (field (name "CREATED BY") "YTL")
      )
      (libsource (lib "*") (part "RESISTOR_Dup1"))
    )
    (comp (ref "R6838")
      (value "*")
      (footprint "R0402")
      (description "НЁУГєсД¤µзЧи,22R,+/-5%,R0402,1/16W.")
      (fields
        (field (name "PCB FOOTPRINT") "R0402")
        (field (name "TOLERANCE") "5%")
        (field (name "MANUFACTURER") "YAGEO")
        (field (name "ALTIUM_UNNAMED_1") "22R")
        (field (name "CREATED BY") "YTL")
      )
      (libsource (lib "*") (part "RESISTOR_Dup1"))
    )
    (comp (ref "R6839")
      (value "*")
      (footprint "R0402")
      (description "НЁУГєсД¤µзЧи,22R,+/-5%,R0402,1/16W.")
      (fields
        (field (name "PCB FOOTPRINT") "R0402")
        (field (name "TOLERANCE") "5%")
        (field (name "MANUFACTURER") "YAGEO")
        (field (name "ALTIUM_UNNAMED_1") "22R")
        (field (name "CREATED BY") "YTL")
      )
      (libsource (lib "*") (part "RESISTOR_Dup1"))
    )
    (comp (ref "R6840")
      (value "*")
      (footprint "R0402")
      (description "НЁУГєсД¤µзЧи,22R,+/-5%,R0402,1/16W.")
      (fields
        (field (name "PCB FOOTPRINT") "R0402")
        (field (name "TOLERANCE") "5%")
        (field (name "MANUFACTURER") "YAGEO")
        (field (name "ALTIUM_UNNAMED_1") "22R")
        (field (name "CREATED BY") "YTL")
      )
      (libsource (lib "*") (part "RESISTOR_Dup1"))
    )
    (comp (ref "R6841")
      (value "*")
      (footprint "R0402")
      (description "НЁУГєсД¤µзЧи,22R,+/-5%,R0402,1/16W.")
      (fields
        (field (name "PCB FOOTPRINT") "R0402")
        (field (name "TOLERANCE") "5%")
        (field (name "MANUFACTURER") "YAGEO")
        (field (name "ALTIUM_UNNAMED_1") "22R")
        (field (name "CREATED BY") "YTL")
      )
      (libsource (lib "*") (part "RESISTOR_Dup1"))
    )
    (comp (ref "R6842")
      (value "*")
      (footprint "R0402")
      (description "НЁУГєсД¤µзЧи,22R,+/-5%,R0402,1/16W.")
      (fields
        (field (name "PCB FOOTPRINT") "R0402")
        (field (name "TOLERANCE") "5%")
        (field (name "MANUFACTURER") "YAGEO")
        (field (name "ALTIUM_UNNAMED_1") "22R")
        (field (name "CREATED BY") "YTL")
      )
      (libsource (lib "*") (part "RESISTOR_Dup1"))
    )
    (comp (ref "TP6800")
      (value "*")
      (footprint "TEST")
      (description "Test Point 0.7mm")
      (fields (field (name "ALTIUM_UNNAMED_1") "TP_0.7") (field (name "CREATED BY") "JJJ"))
      (libsource (lib "*") (part "TP"))
    )
    (comp (ref "U6800")
      (value "*")
      (footprint "SOIC24_17R53X12R20X5R51")
      (description "Gigabit Ethernet (1000Base-T)")
      (fields
        (field (name "PCB FOOTPRINT") "SOIC24_17R53X12R20X5R51")
        (field (name "MANUFACTURER") "Pulse")
        (field (name "ALTIUM_UNNAMED_1") "H5007")
        (field (name "CREATED BY") "JJJ")
      )
      (libsource (lib "*") (part "Ethernet_H5007"))
    )
    (comp (ref "U6801")
      (value "*")
      (footprint "QFN40_5R00X5R00X0R80_T")
      (description "Integrated 10/100/1000 Gigabit Ethernet TransceiverЈ¬Supports IEEE 802.3az-2010,")
      (fields
        (field (name "PCB FOOTPRINT") "QFN40_5R00X5R00X0R90_T")
        (field (name "MANUFACTURER") "RealTek(ИркЕ)")
        (field (name "ALTIUM_UNNAMED_1") "RTL8211F-CG")
        (field (name "CREATED BY") "JJJ")
      )
      (libsource (lib "*") (part "Ethernet_RTL8211F"))
    )
    (comp (ref "Y6800")
      (value "*")
      (footprint "CRY-3225")
      (description "ОЮФґѕ§ХсЈ¬25MЈ¬3225,ЎА10ppmЈ¬10pFЈ¬Hosonic")
      (fields
        (field (name "PCB FOOTPRINT") "CRY4_3R20X2R50X0R80")
        (field (name "MANUFACTURER") "Hosonic(єиРЗµзЧУ)")
        (field (name "ALTIUM_UNNAMED_1") "25MHz")
        (field (name "CREATED BY") "JJJ")
      )
      (libsource (lib "*") (part "CRYSTAL_4P"))
    )
  )
  (nets
    (net (code "1") (name "/LAN1_MCT1") (class "Default")
      (node (ref "D6800") (pin "1") (pinfunction "1_1") (pintype "passive"))
      (node (ref "D6804") (pin "1") (pinfunction "1_1") (pintype "passive"))
      (node (ref "R6813") (pin "1") (pinfunction "1_1") (pintype "passive"))
      (node (ref "U6800") (pin "24") (pinfunction "MCT1_24") (pintype "passive"))
    )
    (net (code "2") (name "/LAN1_MCT2") (class "Default")
      (node (ref "D6801") (pin "1") (pinfunction "1_1") (pintype "passive"))
      (node (ref "D6805") (pin "1") (pinfunction "1_1") (pintype "passive"))
      (node (ref "R6812") (pin "1") (pinfunction "1_1") (pintype "passive"))
      (node (ref "U6800") (pin "21") (pinfunction "MCT2_21") (pintype "passive"))
    )
    (net (code "3") (name "/LAN1_MCT3") (class "Default")
      (node (ref "D6802") (pin "1") (pinfunction "1_1") (pintype "passive"))
      (node (ref "D6806") (pin "1") (pinfunction "1_1") (pintype "passive"))
      (node (ref "R6811") (pin "1") (pinfunction "1_1") (pintype "passive"))
      (node (ref "U6800") (pin "18") (pinfunction "MCT3_18") (pintype "passive"))
    )
    (net (code "4") (name "/LAN1_MCT4") (class "Default")
      (node (ref "D6803") (pin "1") (pinfunction "1_1") (pintype "passive"))
      (node (ref "D6807") (pin "1") (pinfunction "1_1") (pintype "passive"))
      (node (ref "R6810") (pin "1") (pinfunction "1_1") (pintype "passive"))
      (node (ref "U6800") (pin "15") (pinfunction "MCT4_15") (pintype "passive"))
    )
    (net (code "5") (name "/PHY1_CLKOUT125") (class "Default")
      (node (ref "R6814") (pin "2") (pinfunction "2_2") (pintype "passive"))
      (node (ref "U6801") (pin "35") (pinfunction "CLKOUT_35") (pintype "passive"))
    )
    (net (code "6") (name "/PHY1_LED0{slash}CFG_EXT") (class "Default")
      (node (ref "R6816") (pin "1") (pinfunction "1_1") (pintype "passive"))
      (node (ref "R6817") (pin "2") (pinfunction "2_2") (pintype "passive"))
      (node (ref "U6801") (pin "32") (pinfunction "LED0/CFG_EXT_32") (pintype "passive"))
    )
    (net (code "7") (name "/PHY1_LED1{slash}CFG_LDO0") (class "Default")
      (node (ref "R6820") (pin "1") (pinfunction "1_1") (pintype "passive"))
      (node (ref "U6801") (pin "33") (pinfunction "LED1/CFG_LDO0_33") (pintype "passive"))
    )
    (net (code "8") (name "/PHY1_LED2{slash}CFG_LDO1") (class "Default")
      (node (ref "R6818") (pin "1") (pinfunction "1_1") (pintype "passive"))
      (node (ref "R6819") (pin "2") (pinfunction "2_2") (pintype "passive"))
      (node (ref "U6801") (pin "34") (pinfunction "LED2/CFG_LDO1_34") (pintype "passive"))
    )
    (net (code "9") (name "/PHY1_MDI0+") (class "Default")
      (node (ref "R6808") (pin "1") (pinfunction "1_1") (pintype "passive"))
      (node (ref "U6801") (pin "1") (pinfunction "MDI[0]+_1") (pintype "passive"))
    )
    (net (code "10") (name "/PHY1_MDI0-") (class "Default")
      (node (ref "R6807") (pin "1") (pinfunction "1_1") (pintype "passive"))
      (node (ref "U6801") (pin "2") (pinfunction "MDI[0]-_2") (pintype "passive"))
    )
    (net (code "11") (name "/PHY1_MDI1+") (class "Default")
      (node (ref "R6806") (pin "1") (pinfunction "1_1") (pintype "passive"))
      (node (ref "U6801") (pin "4") (pinfunction "MDI[1]+_4") (pintype "passive"))
    )
    (net (code "12") (name "/PHY1_MDI1-") (class "Default")
      (node (ref "R6805") (pin "1") (pinfunction "1_1") (pintype "passive"))
      (node (ref "U6801") (pin "5") (pinfunction "MDI[1]-_5") (pintype "passive"))
    )
    (net (code "13") (name "/PHY1_MDI2+") (class "Default")
      (node (ref "R6804") (pin "1") (pinfunction "1_1") (pintype "passive"))
      (node (ref "U6801") (pin "6") (pinfunction "MDI[2]+_6") (pintype "passive"))
    )
    (net (code "14") (name "/PHY1_MDI2-") (class "Default")
      (node (ref "R6803") (pin "1") (pinfunction "1_1") (pintype "passive"))
      (node (ref "U6801") (pin "7") (pinfunction "MDI[2]-_7") (pintype "passive"))
    )
    (net (code "15") (name "/PHY1_MDI3+") (class "Default")
      (node (ref "R6801") (pin "1") (pinfunction "1_1") (pintype "passive"))
      (node (ref "U6801") (pin "9") (pinfunction "MDI[3]+_9") (pintype "passive"))
    )
    (net (code "16") (name "/PHY1_MDI3-") (class "Default")
      (node (ref "R6800") (pin "1") (pinfunction "1_1") (pintype "passive"))
      (node (ref "U6801") (pin "10") (pinfunction "MDI[3]-_10") (pintype "passive"))
    )
    (net (code "17") (name "/PHY1_MDI_0+") (class "Default")
      (node (ref "ED6803") (pin "2") (pinfunction "2_2") (pintype "passive"))
      (node (ref "R6808") (pin "2") (pinfunction "2_2") (pintype "passive"))
      (node (ref "U6800") (pin "12") (pinfunction "TD4-_12") (pintype "passive"))
    )
    (net (code "18") (name "/PHY1_MDI_0-") (class "Default")
      (node (ref "ED6803") (pin "1") (pinfunction "1_1") (pintype "passive"))
      (node (ref "R6807") (pin "2") (pinfunction "2_2") (pintype "passive"))
      (node (ref "U6800") (pin "11") (pinfunction "TD4+_11") (pintype "passive"))
    )
    (net (code "19") (name "/PHY1_MDI_1+") (class "Default")
      (node (ref "ED6802") (pin "2") (pinfunction "2_2") (pintype "passive"))
      (node (ref "R6806") (pin "2") (pinfunction "2_2") (pintype "passive"))
      (node (ref "U6800") (pin "9") (pinfunction "TD3-_9") (pintype "passive"))
    )
    (net (code "20") (name "/PHY1_MDI_1-") (class "Default")
      (node (ref "ED6802") (pin "1") (pinfunction "1_1") (pintype "passive"))
      (node (ref "R6805") (pin "2") (pinfunction "2_2") (pintype "passive"))
      (node (ref "U6800") (pin "8") (pinfunction "TD3+_8") (pintype "passive"))
    )
    (net (code "21") (name "/PHY1_MDI_2+") (class "Default")
      (node (ref "ED6801") (pin "2") (pinfunction "2_2") (pintype "passive"))
      (node (ref "R6804") (pin "2") (pinfunction "2_2") (pintype "passive"))
      (node (ref "U6800") (pin "6") (pinfunction "TD2-_6") (pintype "passive"))
    )
    (net (code "22") (name "/PHY1_MDI_2-") (class "Default")
      (node (ref "ED6801") (pin "1") (pinfunction "1_1") (pintype "passive"))
      (node (ref "R6803") (pin "2") (pinfunction "2_2") (pintype "passive"))
      (node (ref "U6800") (pin "5") (pinfunction "TD2+_5") (pintype "passive"))
    )
    (net (code "23") (name "/PHY1_MDI_3+") (class "Default")
      (node (ref "ED6800") (pin "2") (pinfunction "2_2") (pintype "passive"))
      (node (ref "R6801") (pin "2") (pinfunction "2_2") (pintype "passive"))
      (node (ref "U6800") (pin "3") (pinfunction "TD1-_3") (pintype "passive"))
    )
    (net (code "24") (name "/PHY1_MDI_3-") (class "Default")
      (node (ref "ED6800") (pin "1") (pinfunction "1_1") (pintype "passive"))
      (node (ref "R6800") (pin "2") (pinfunction "2_2") (pintype "passive"))
      (node (ref "U6800") (pin "2") (pinfunction "TD1+_2") (pintype "passive"))
    )
    (net (code "25") (name "/PHY1_REG_OUT") (class "Default")
      (node (ref "L6800") (pin "1") (pinfunction "1_1") (pintype "passive"))
      (node (ref "U6801") (pin "30") (pinfunction "REG_OUT_30") (pintype "passive"))
    )
    (net (code "26") (name "/PHY1_RSTn") (class "Default")
      (node (ref "C6817") (pin "1") (pinfunction "1_1") (pintype "passive"))
      (node (ref "R6834") (pin "2") (pinfunction "2_2") (pintype "passive"))
      (node (ref "R6836") (pin "2") (pinfunction "2_2") (pintype "passive"))
      (node (ref "U6801") (pin "12") (pinfunction "PHYRSTB_12") (pintype "passive"))
    )
    (net (code "27") (name "/PHY1_RXCLK{slash}PHYAD1") (class "Default")
      (node (ref "R6823") (pin "1") (pinfunction "1_1") (pintype "passive"))
      (node (ref "R6824") (pin "2") (pinfunction "2_2") (pintype "passive"))
      (node (ref "R6841") (pin "1") (pinfunction "1_1") (pintype "passive"))
      (node (ref "U6801") (pin "27") (pinfunction "RXC/PHYAD1_27") (pintype "passive"))
    )
    (net (code "28") (name "/PHY1_RXD0{slash}RXDLY") (class "Default")
      (node (ref "R6826") (pin "1") (pinfunction "1_1") (pintype "passive"))
      (node (ref "R6827") (pin "2") (pinfunction "2_2") (pintype "passive"))
      (node (ref "R6837") (pin "1") (pinfunction "1_1") (pintype "passive"))
      (node (ref "U6801") (pin "25") (pinfunction "RXD0/RXDLY_25") (pintype "passive"))
    )
    (net (code "29") (name "/PHY1_RXD1{slash}TXDLY") (class "Default")
      (node (ref "R6828") (pin "1") (pinfunction "1_1") (pintype "passive"))
      (node (ref "R6829") (pin "2") (pinfunction "2_2") (pintype "passive"))
      (node (ref "R6838") (pin "1") (pinfunction "1_1") (pintype "passive"))
      (node (ref "U6801") (pin "24") (pinfunction "RXD1/TXDLY_24") (pintype "passive"))
    )
    (net (code "30") (name "/PHY1_RXD2{slash}PLLOFF") (class "Default")
      (node (ref "R6831") (pin "1") (pinfunction "1_1") (pintype "passive"))
      (node (ref "R6832") (pin "2") (pinfunction "2_2") (pintype "passive"))
      (node (ref "R6839") (pin "1") (pinfunction "1_1") (pintype "passive"))
      (node (ref "U6801") (pin "23") (pinfunction "RXD2/PLLOFF_23") (pintype "passive"))
    )
    (net (code "31") (name "/PHY1_RXD3{slash}PHYAD0") (class "Default")
      (node (ref "R6822") (pin "2") (pinfunction "2_2") (pintype "passive"))
      (node (ref "R6840") (pin "1") (pinfunction "1_1") (pintype "passive"))
      (node (ref "U6801") (pin "22") (pinfunction "RXD3/PHYAD0_22") (pintype "passive"))
    )
    (net (code "32") (name "/PHY1_RXDV{slash}PHYAD2") (class "Default")
      (node (ref "R6825") (pin "1") (pinfunction "1_1") (pintype "passive"))
      (node (ref "R6842") (pin "1") (pinfunction "1_1") (pintype "passive"))
      (node (ref "U6801") (pin "26") (pinfunction "RXCTL/PHYAD2_26") (pintype "passive"))
    )
    (net (code "33") (name "/PHY1_XTALIN") (class "Default")
      (node (ref "C6800") (pin "1") (pinfunction "1_1") (pintype "passive"))
      (node (ref "R6802") (pin "1") (pinfunction "1_1") (pintype "passive"))
      (node (ref "U6801") (pin "36") (pinfunction "XTAL_IN_36") (pintype "passive"))
      (node (ref "Y6800") (pin "3") (pinfunction "X2_3") (pintype "passive"))
    )
    (net (code "34") (name "/PHY1_XTALOUT") (class "Default")
      (node (ref "C6801") (pin "1") (pinfunction "1_1") (pintype "passive"))
      (node (ref "R6809") (pin "2") (pinfunction "2_2") (pintype "passive"))
      (node (ref "U6801") (pin "37") (pinfunction "XTAL_OUT/EXT_CLK_37") (pintype "passive"))
      (node (ref "Y6800") (pin "1") (pinfunction "X1_1") (pintype "passive"))
    )
    (net (code "35") (name "/RSET1") (class "Default")
      (node (ref "R6821") (pin "1") (pinfunction "1_1") (pintype "passive"))
      (node (ref "U6801") (pin "39") (pinfunction "RSET_39") (pintype "passive"))
    )
    (net (code "36") (name "ETH1_REFCLKO_25M") (class "Default")
      (node (ref "R6809") (pin "1") (pinfunction "1_1") (pintype "passive"))
    )
    (net (code "37") (name "GMAC1_MCLKINOUT") (class "Default")
      (node (ref "C6806") (pin "1") (pinfunction "1_1") (pintype "passive"))
      (node (ref "R6814") (pin "1") (pinfunction "1_1") (pintype "passive"))
      (node (ref "R6815") (pin "1") (pinfunction "1_1") (pintype "passive"))
    )
    (net (code "38") (name "GMAC1_MDC") (class "Default")
      (node (ref "U6801") (pin "13") (pinfunction "MDC_13") (pintype "passive"))
    )
    (net (code "39") (name "GMAC1_MDIO") (class "Default")
      (node (ref "R6835") (pin "2") (pinfunction "2_2") (pintype "passive"))
      (node (ref "U6801") (pin "14") (pinfunction "MDIO_14") (pintype "passive"))
    )
    (net (code "40") (name "GMAC1_RSTn_L_GPIO4_A2") (class "Default")
      (node (ref "R6836") (pin "1") (pinfunction "1_1") (pintype "passive"))
    )
    (net (code "41") (name "GMAC1_RXCLK") (class "Default")
      (node (ref "C6823") (pin "1") (pinfunction "1_1") (pintype "passive"))
      (node (ref "R6841") (pin "2") (pinfunction "2_2") (pintype "passive"))
    )
    (net (code "42") (name "GMAC1_RXD0") (class "Default")
      (node (ref "R6837") (pin "2") (pinfunction "2_2") (pintype "passive"))
    )
    (net (code "43") (name "GMAC1_RXD1") (class "Default")
      (node (ref "R6838") (pin "2") (pinfunction "2_2") (pintype "passive"))
    )
    (net (code "44") (name "GMAC1_RXD2") (class "Default")
      (node (ref "R6839") (pin "2") (pinfunction "2_2") (pintype "passive"))
    )
    (net (code "45") (name "GMAC1_RXD3") (class "Default")
      (node (ref "R6840") (pin "2") (pinfunction "2_2") (pintype "passive"))
    )
    (net (code "46") (name "GMAC1_RXDV_CRS") (class "Default")
      (node (ref "R6842") (pin "2") (pinfunction "2_2") (pintype "passive"))
    )
    (net (code "47") (name "GMAC1_TXCLK") (class "Default")
      (node (ref "C6826") (pin "1") (pinfunction "1_1") (pintype "passive"))
      (node (ref "U6801") (pin "20") (pinfunction "TXC_20") (pintype "passive"))
    )
    (net (code "48") (name "GMAC1_TXD0") (class "Default")
      (node (ref "U6801") (pin "18") (pinfunction "TXD0_18") (pintype "passive"))
    )
    (net (code "49") (name "GMAC1_TXD1") (class "Default")
      (node (ref "U6801") (pin "17") (pinfunction "TXD1_17") (pintype "passive"))
    )
    (net (code "50") (name "GMAC1_TXD2") (class "Default")
      (node (ref "U6801") (pin "16") (pinfunction "TXD2_16") (pintype "passive"))
    )
    (net (code "51") (name "GMAC1_TXD3") (class "Default")
      (node (ref "U6801") (pin "15") (pinfunction "TXD3_15") (pintype "passive"))
    )
    (net (code "52") (name "GMAC1_TXEN") (class "Default")
      (node (ref "U6801") (pin "19") (pinfunction "TXCTL_19") (pintype "passive"))
    )
    (net (code "53") (name "GND") (class "Default")
      (node (ref "C6800") (pin "2") (pinfunction "2_2") (pintype "passive"))
      (node (ref "C6801") (pin "2") (pinfunction "2_2") (pintype "passive"))
      (node (ref "C6802") (pin "2") (pinfunction "2_2") (pintype "passive"))
      (node (ref "C6803") (pin "2") (pinfunction "2_2") (pintype "passive"))
      (node (ref "C6804") (pin "2") (pinfunction "2_2") (pintype "passive"))
      (node (ref "C6805") (pin "2") (pinfunction "2_2") (pintype "passive"))
      (node (ref "C6806") (pin "2") (pinfunction "2_2") (pintype "passive"))
      (node (ref "C6807") (pin "2") (pinfunction "2_2") (pintype "passive"))
      (node (ref "C6808") (pin "2") (pinfunction "2_2") (pintype "passive"))
      (node (ref "C6809") (pin "2") (pinfunction "2_2") (pintype "passive"))
      (node (ref "C6810") (pin "2") (pinfunction "2_2") (pintype "passive"))
      (node (ref "C6811") (pin "2") (pinfunction "2_2") (pintype "passive"))
      (node (ref "C6812") (pin "2") (pinfunction "2_2") (pintype "passive"))
      (node (ref "C6813") (pin "2") (pinfunction "2_2") (pintype "passive"))
      (node (ref "C6814") (pin "2") (pinfunction "2_2") (pintype "passive"))
      (node (ref "C6815") (pin "2") (pinfunction "2_2") (pintype "passive"))
      (node (ref "C6816") (pin "2") (pinfunction "2_2") (pintype "passive"))
      (node (ref "C6817") (pin "2") (pinfunction "2_2") (pintype "passive"))
      (node (ref "C6818") (pin "2") (pinfunction "2_2") (pintype "passive"))
      (node (ref "C6819") (pin "2") (pinfunction "2_2") (pintype "passive"))
      (node (ref "C6820") (pin "2") (pinfunction "2_2") (pintype "passive"))
      (node (ref "C6821") (pin "2") (pinfunction "2_2") (pintype "passive"))
      (node (ref "C6822") (pin "2") (pinfunction "2_2") (pintype "passive"))
      (node (ref "C6823") (pin "2") (pinfunction "2_2") (pintype "passive"))
      (node (ref "C6826") (pin "2") (pinfunction "2_2") (pintype "passive"))
      (node (ref "D6800") (pin "2") (pinfunction "2_2") (pintype "passive"))
      (node (ref "D6801") (pin "2") (pinfunction "2_2") (pintype "passive"))
      (node (ref "D6802") (pin "2") (pinfunction "2_2") (pintype "passive"))
      (node (ref "D6803") (pin "2") (pinfunction "2_2") (pintype "passive"))
      (node (ref "D6804") (pin "2") (pinfunction "2_2") (pintype "passive"))
      (node (ref "D6805") (pin "2") (pinfunction "2_2") (pintype "passive"))
      (node (ref "D6806") (pin "2") (pinfunction "2_2") (pintype "passive"))
      (node (ref "D6807") (pin "2") (pinfunction "2_2") (pintype "passive"))
      (node (ref "R6802") (pin "2") (pinfunction "2_2") (pintype "passive"))
      (node (ref "R6815") (pin "2") (pinfunction "2_2") (pintype "passive"))
      (node (ref "R6816") (pin "2") (pinfunction "2_2") (pintype "passive"))
      (node (ref "R6818") (pin "2") (pinfunction "2_2") (pintype "passive"))
      (node (ref "R6820") (pin "2") (pinfunction "2_2") (pintype "passive"))
      (node (ref "R6821") (pin "2") (pinfunction "2_2") (pintype "passive"))
      (node (ref "R6823") (pin "2") (pinfunction "2_2") (pintype "passive"))
      (node (ref "R6825") (pin "2") (pinfunction "2_2") (pintype "passive"))
      (node (ref "R6826") (pin "2") (pinfunction "2_2") (pintype "passive"))
      (node (ref "R6828") (pin "2") (pinfunction "2_2") (pintype "passive"))
      (node (ref "R6831") (pin "2") (pinfunction "2_2") (pintype "passive"))
      (node (ref "U6801") (pin "41") (pinfunction "E_Pad_41") (pintype "passive"))
      (node (ref "Y6800") (pin "2") (pinfunction "GND_2") (pintype "power_in"))
      (node (ref "Y6800") (pin "4") (pinfunction "GND_4") (pintype "power_in"))
    )
    (net (code "54") (name "LAN1_A+") (class "Default")
      (node (ref "U6800") (pin "13") (pinfunction "MX4-_13") (pintype "passive"))
    )
    (net (code "55") (name "LAN1_A-") (class "Default")
      (node (ref "U6800") (pin "14") (pinfunction "MX4+_14") (pintype "passive"))
    )
    (net (code "56") (name "LAN1_B+") (class "Default")
      (node (ref "U6800") (pin "16") (pinfunction "MX3-_16") (pintype "passive"))
    )
    (net (code "57") (name "LAN1_B-") (class "Default")
      (node (ref "U6800") (pin "17") (pinfunction "MX3+_17") (pintype "passive"))
    )
    (net (code "58") (name "LAN1_C+") (class "Default")
      (node (ref "U6800") (pin "19") (pinfunction "MX2-_19") (pintype "passive"))
    )
    (net (code "59") (name "LAN1_C-") (class "Default")
      (node (ref "U6800") (pin "20") (pinfunction "MX2+_20") (pintype "passive"))
    )
    (net (code "60") (name "LAN1_D+") (class "Default")
      (node (ref "U6800") (pin "22") (pinfunction "MX1-_22") (pintype "passive"))
    )
    (net (code "61") (name "LAN1_D-") (class "Default")
      (node (ref "U6800") (pin "23") (pinfunction "MX1+_23") (pintype "passive"))
    )
    (net (code "62") (name "Net-(C6807-Pad1)") (class "Default")
      (node (ref "C6807") (pin "1") (pinfunction "1_1") (pintype "passive"))
      (node (ref "R6810") (pin "2") (pinfunction "2_2") (pintype "passive"))
      (node (ref "R6811") (pin "2") (pinfunction "2_2") (pintype "passive"))
      (node (ref "R6812") (pin "2") (pinfunction "2_2") (pintype "passive"))
      (node (ref "R6813") (pin "2") (pinfunction "2_2") (pintype "passive"))
    )
    (net (code "63") (name "Net-(U6800-TCT1)") (class "Default")
      (node (ref "C6802") (pin "1") (pinfunction "1_1") (pintype "passive"))
      (node (ref "C6803") (pin "1") (pinfunction "1_1") (pintype "passive"))
      (node (ref "C6804") (pin "1") (pinfunction "1_1") (pintype "passive"))
      (node (ref "C6805") (pin "1") (pinfunction "1_1") (pintype "passive"))
      (node (ref "U6800") (pin "1") (pinfunction "TCT1_1") (pintype "passive"))
      (node (ref "U6800") (pin "10") (pinfunction "TCT4_10") (pintype "passive"))
      (node (ref "U6800") (pin "4") (pinfunction "TCT2_4") (pintype "passive"))
      (node (ref "U6800") (pin "7") (pinfunction "TCT3_7") (pintype "passive"))
    )
    (net (code "64") (name "Net-(U6801-INTB{slash}PMEB)") (class "Default")
      (node (ref "TP6800") (pin "1") (pinfunction "1_1") (pintype "passive"))
      (node (ref "U6801") (pin "31") (pinfunction "INTB/PMEB_31") (pintype "passive"))
    )
    (net (code "65") (name "VCC3V3_PHY1") (class "Default")
      (node (ref "C6811") (pin "1") (pinfunction "1_1") (pintype "passive"))
      (node (ref "C6812") (pin "1") (pinfunction "1_1") (pintype "passive"))
      (node (ref "C6813") (pin "1") (pinfunction "1_1") (pintype "passive"))
      (node (ref "C6818") (pin "1") (pinfunction "1_1") (pintype "passive"))
      (node (ref "C6819") (pin "1") (pinfunction "1_1") (pintype "passive"))
      (node (ref "R6817") (pin "1") (pinfunction "1_1") (pintype "passive"))
      (node (ref "R6819") (pin "1") (pinfunction "1_1") (pintype "passive"))
      (node (ref "R6833") (pin "2") (pinfunction "2_2") (pintype "passive"))
      (node (ref "R6834") (pin "1") (pinfunction "1_1") (pintype "passive"))
      (node (ref "U6801") (pin "11") (pinfunction "AVDD33_11") (pintype "power_in"))
      (node (ref "U6801") (pin "29") (pinfunction "DVDD33_29") (pintype "power_in"))
      (node (ref "U6801") (pin "40") (pinfunction "AVDD33_40") (pintype "power_in"))
    )
    (net (code "66") (name "VCCIO_PHY1") (class "Default")
      (node (ref "C6808") (pin "1") (pinfunction "1_1") (pintype "passive"))
      (node (ref "C6809") (pin "1") (pinfunction "1_1") (pintype "passive"))
      (node (ref "C6810") (pin "1") (pinfunction "1_1") (pintype "passive"))
      (node (ref "R6822") (pin "1") (pinfunction "1_1") (pintype "passive"))
      (node (ref "R6824") (pin "1") (pinfunction "1_1") (pintype "passive"))
      (node (ref "R6827") (pin "1") (pinfunction "1_1") (pintype "passive"))
      (node (ref "R6829") (pin "1") (pinfunction "1_1") (pintype "passive"))
      (node (ref "R6830") (pin "2") (pinfunction "2_2") (pintype "passive"))
      (node (ref "R6832") (pin "1") (pinfunction "1_1") (pintype "passive"))
      (node (ref "R6835") (pin "1") (pinfunction "1_1") (pintype "passive"))
      (node (ref "U6801") (pin "28") (pinfunction "DVDD_RG_28") (pintype "passive"))
    )
    (net (code "67") (name "VCC_3V3") (class "Default")
      (node (ref "R6830") (pin "1") (pinfunction "1_1") (pintype "passive"))
      (node (ref "R6833") (pin "1") (pinfunction "1_1") (pintype "passive"))
    )
    (net (code "68") (name "VDD10_PHY1") (class "Default")
      (node (ref "C6814") (pin "1") (pinfunction "1_1") (pintype "passive"))
      (node (ref "C6815") (pin "1") (pinfunction "1_1") (pintype "passive"))
      (node (ref "C6816") (pin "1") (pinfunction "1_1") (pintype "passive"))
      (node (ref "C6820") (pin "1") (pinfunction "1_1") (pintype "passive"))
      (node (ref "C6821") (pin "1") (pinfunction "1_1") (pintype "passive"))
      (node (ref "C6822") (pin "1") (pinfunction "1_1") (pintype "passive"))
      (node (ref "L6800") (pin "2") (pinfunction "2_2") (pintype "passive"))
      (node (ref "U6801") (pin "21") (pinfunction "DVDD10_21") (pintype "power_in"))
      (node (ref "U6801") (pin "3") (pinfunction "AVDD10_3") (pintype "power_in"))
      (node (ref "U6801") (pin "38") (pinfunction "AVDD10_38") (pintype "power_in"))
      (node (ref "U6801") (pin "8") (pinfunction "AVDD10_8") (pintype "power_in"))
    )
  )
)
